# DS2481-100-Test1.net
KiCad netlist of a schematic drawn in EAGLE
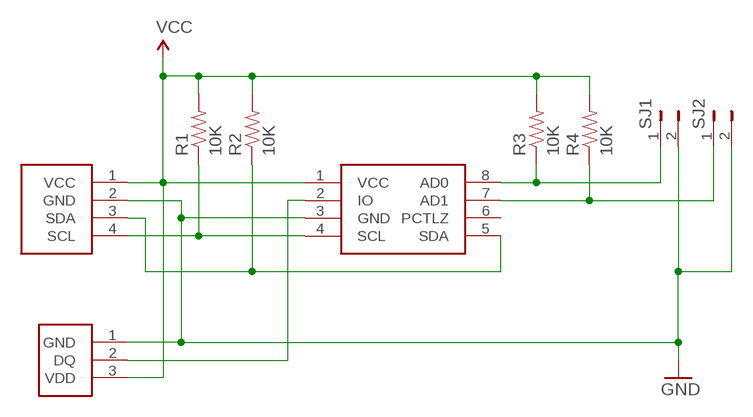
[diagram p0: schematic, sheet 1]

(export (version "E")
  (design (tool "Eeschema 10.0.6"))
  (components
    (comp (ref "R1")
      (value "10K")
      (footprint "eagle-import:0603-RES")
      (libsource (lib "eagle-import") (part "RES-10K-06030603"))
    )
    (comp (ref "R2")
      (value "10K")
      (footprint "eagle-import:0603-RES")
      (libsource (lib "eagle-import") (part "RES-10K-06030603"))
    )
    (comp (ref "R3")
      (value "10K")
      (footprint "eagle-import:0603-RES")
      (libsource (lib "eagle-import") (part "RES-10K-06030603"))
    )
    (comp (ref "R4")
      (value "10K")
      (footprint "eagle-import:0603-RES")
      (libsource (lib "eagle-import") (part "RES-10K-06030603"))
    )
    (comp (ref "SJ1")
      (value "JUMPER-PTH-2-NO")
      (footprint "eagle-import:PTH-JUMPER-2-NO_NO_SILK")
      (libsource (lib "eagle-import") (part "JUMPER-PTH-2-NO"))
    )
    (comp (ref "SJ2")
      (value "JUMPER-PTH-2-NO")
      (footprint "eagle-import:PTH-JUMPER-2-NO_NO_SILK")
      (libsource (lib "eagle-import") (part "JUMPER-PTH-2-NO"))
    )
    (comp (ref "U$1")
      (value "HEADER-I2C-PWR")
      (footprint "eagle-import:HEADER-I2C-PWR")
      (libsource (lib "eagle-import") (part "HEADER-I2C-PWR"))
    )
    (comp (ref "U$2")
      (value "DS2482-100")
      (footprint "eagle-import:8-SOIC-MAXIM")
      (libsource (lib "eagle-import") (part "DS2482-100"))
    )
    (comp (ref "U$3")
      (value "TERMBLOCK-1WIRE")
      (footprint "eagle-import:TERMBLOCK-1WIRE")
      (libsource (lib "eagle-import") (part "TERMBLOCK-1WIRE"))
    )
  )
  (nets
    (net (code "1") (name "GND") (class "Default")
      (node (ref "SJ1") (pin "2") (pinfunction "2_2") (pintype "passive"))
      (node (ref "SJ2") (pin "2") (pinfunction "2_2") (pintype "passive"))
      (node (ref "U$1") (pin "2") (pinfunction "GND_2") (pintype "passive"))
      (node (ref "U$2") (pin "3") (pinfunction "GND_3") (pintype "power_in"))
      (node (ref "U$3") (pin "1") (pinfunction "GND_1") (pintype "power_in"))
    )
    (net (code "2") (name "Net-(U$1-SCL)") (class "Default")
      (node (ref "R1") (pin "1") (pinfunction "1_1") (pintype "passive"))
      (node (ref "U$1") (pin "4") (pinfunction "SCL_4") (pintype "passive"))
      (node (ref "U$2") (pin "4") (pinfunction "SCL_4") (pintype "bidirectional"))
    )
    (net (code "3") (name "Net-(U$1-SDA)") (class "Default")
      (node (ref "R2") (pin "1") (pinfunction "1_1") (pintype "passive"))
      (node (ref "U$1") (pin "3") (pinfunction "SDA_3") (pintype "passive"))
      (node (ref "U$2") (pin "5") (pinfunction "SDA_5") (pintype "bidirectional"))
    )
    (net (code "4") (name "Net-(U$2-AD0)") (class "Default")
      (node (ref "R3") (pin "1") (pinfunction "1_1") (pintype "passive"))
      (node (ref "SJ1") (pin "1") (pinfunction "1_1") (pintype "passive"))
      (node (ref "U$2") (pin "8") (pinfunction "AD0_8") (pintype "input"))
    )
    (net (code "5") (name "Net-(U$2-AD1)") (class "Default")
      (node (ref "R4") (pin "1") (pinfunction "1_1") (pintype "passive"))
      (node (ref "SJ2") (pin "1") (pinfunction "1_1") (pintype "passive"))
      (node (ref "U$2") (pin "7") (pinfunction "AD1_7") (pintype "input"))
    )
    (net (code "6") (name "Net-(U$2-IO)") (class "Default")
      (node (ref "U$2") (pin "2") (pinfunction "IO_2") (pintype "bidirectional"))
      (node (ref "U$3") (pin "2") (pinfunction "DQ_2") (pintype "bidirectional"))
    )
    (net (code "7") (name "VCC") (class "Default")
      (node (ref "R1") (pin "2") (pinfunction "2_2") (pintype "passive"))
      (node (ref "R2") (pin "2") (pinfunction "2_2") (pintype "passive"))
      (node (ref "R3") (pin "2") (pinfunction "2_2") (pintype "passive"))
      (node (ref "R4") (pin "2") (pinfunction "2_2") (pintype "passive"))
      (node (ref "U$1") (pin "1") (pinfunction "VCC_1") (pintype "passive"))
      (node (ref "U$2") (pin "1") (pinfunction "VCC_1") (pintype "power_in"))
      (node (ref "U$3") (pin "3") (pinfunction "VDD_3") (pintype "power_in"))
    )
    (net (code "8") (name "unconnected-(U$2-PCTLZ-Pad6)") (class "Default")
      (node (ref "U$2") (pin "6") (pinfunction "PCTLZ_6") (pintype "output"))
    )
  )
)
